# MCU_PWR.net
KiCad netlist of a schematic drawn in Altium Designer
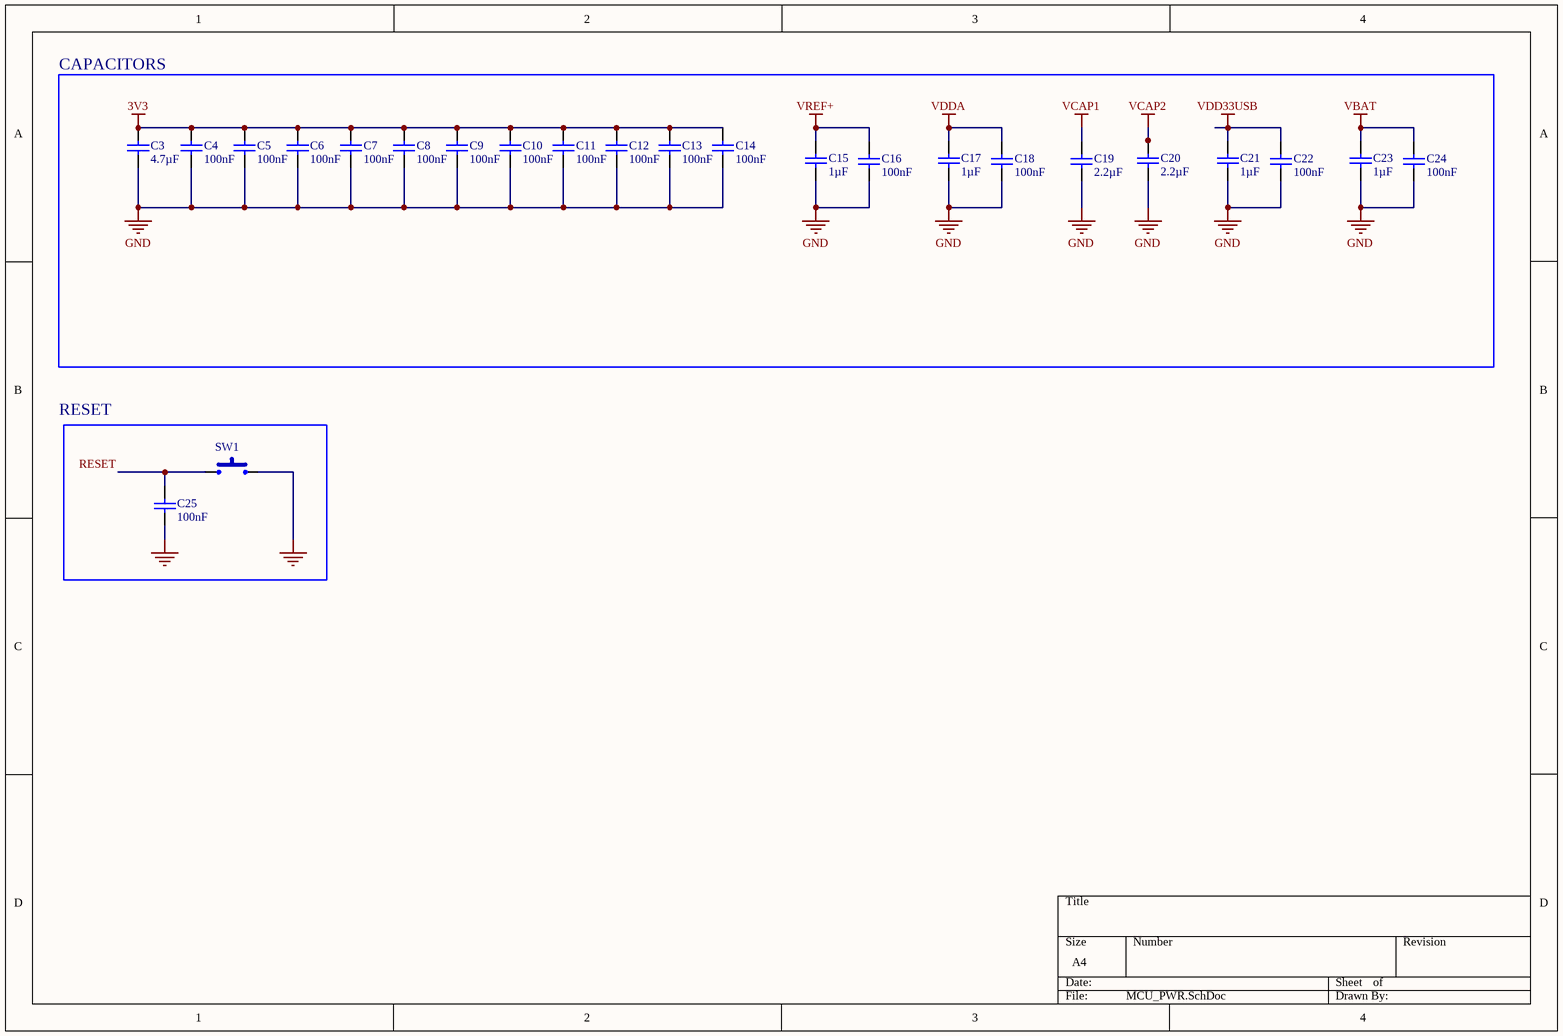
[diagram p0: MCU_PWR.SchDoc]

(export (version "E")
  (design (tool "Eeschema 10.0.6"))
  (components
    (comp (ref "C3")
      (value "4.7µF")
      (footprint "WCAP-CSGP_0603_L1.6W0.8H0.8_Reflow")
      (description "WCAP-CSGP Multilayer Ceramic Chip Capacitor, General Purpose, size 0603, X5R, 4.7uF, 10VDC")
      (fields
        (field (name "MANUFACTURER PART NUMBER") "885012106012")
        (field (name "MANUFACTURER") "Wurth Elektronik")
      )
      (libsource (lib "LEEM UPM") (part "885012209047R"))
    )
    (comp (ref "C4")
      (value "100nF")
      (footprint "WCAP-CSGP_0603_L1.6W0.8H0.8_Reflow")
      (description "WCAP-CSGP Multilayer Ceramic Chip Capacitor, General Purpose, size 0603, X7R, 100nF, 25VDC")
      (fields
        (field (name "MANUFACTURER") "Wurth Elektronik")
        (field (name "MANUFACTURER PART NUMBER") "885012206071")
      )
      (libsource (lib "LEEM UPM") (part "885012209047R"))
    )
    (comp (ref "C5")
      (value "100nF")
      (footprint "WCAP-CSGP_0603_L1.6W0.8H0.8_Reflow")
      (description "WCAP-CSGP Multilayer Ceramic Chip Capacitor, General Purpose, size 0603, X7R, 100nF, 25VDC")
      (fields
        (field (name "MANUFACTURER") "Wurth Elektronik")
        (field (name "MANUFACTURER PART NUMBER") "885012206071")
      )
      (libsource (lib "LEEM UPM") (part "885012209047R"))
    )
    (comp (ref "C6")
      (value "100nF")
      (footprint "WCAP-CSGP_0603_L1.6W0.8H0.8_Reflow")
      (description "WCAP-CSGP Multilayer Ceramic Chip Capacitor, General Purpose, size 0603, X7R, 100nF, 25VDC")
      (fields
        (field (name "MANUFACTURER") "Wurth Elektronik")
        (field (name "MANUFACTURER PART NUMBER") "885012206071")
      )
      (libsource (lib "LEEM UPM") (part "885012209047R"))
    )
    (comp (ref "C7")
      (value "100nF")
      (footprint "WCAP-CSGP_0603_L1.6W0.8H0.8_Reflow")
      (description "WCAP-CSGP Multilayer Ceramic Chip Capacitor, General Purpose, size 0603, X7R, 100nF, 25VDC")
      (fields
        (field (name "MANUFACTURER") "Wurth Elektronik")
        (field (name "MANUFACTURER PART NUMBER") "885012206071")
      )
      (libsource (lib "LEEM UPM") (part "885012209047R"))
    )
    (comp (ref "C8")
      (value "100nF")
      (footprint "WCAP-CSGP_0603_L1.6W0.8H0.8_Reflow")
      (description "WCAP-CSGP Multilayer Ceramic Chip Capacitor, General Purpose, size 0603, X7R, 100nF, 25VDC")
      (fields
        (field (name "MANUFACTURER") "Wurth Elektronik")
        (field (name "MANUFACTURER PART NUMBER") "885012206071")
      )
      (libsource (lib "LEEM UPM") (part "885012209047R"))
    )
    (comp (ref "C9")
      (value "100nF")
      (footprint "WCAP-CSGP_0603_L1.6W0.8H0.8_Reflow")
      (description "WCAP-CSGP Multilayer Ceramic Chip Capacitor, General Purpose, size 0603, X7R, 100nF, 25VDC")
      (fields
        (field (name "MANUFACTURER") "Wurth Elektronik")
        (field (name "MANUFACTURER PART NUMBER") "885012206071")
      )
      (libsource (lib "LEEM UPM") (part "885012209047R"))
    )
    (comp (ref "C10")
      (value "100nF")
      (footprint "WCAP-CSGP_0603_L1.6W0.8H0.8_Reflow")
      (description "WCAP-CSGP Multilayer Ceramic Chip Capacitor, General Purpose, size 0603, X7R, 100nF, 25VDC")
      (fields
        (field (name "MANUFACTURER") "Wurth Elektronik")
        (field (name "MANUFACTURER PART NUMBER") "885012206071")
      )
      (libsource (lib "LEEM UPM") (part "885012209047R"))
    )
    (comp (ref "C11")
      (value "100nF")
      (footprint "WCAP-CSGP_0603_L1.6W0.8H0.8_Reflow")
      (description "WCAP-CSGP Multilayer Ceramic Chip Capacitor, General Purpose, size 0603, X7R, 100nF, 25VDC")
      (fields
        (field (name "MANUFACTURER") "Wurth Elektronik")
        (field (name "MANUFACTURER PART NUMBER") "885012206071")
      )
      (libsource (lib "LEEM UPM") (part "885012209047R"))
    )
    (comp (ref "C12")
      (value "100nF")
      (footprint "WCAP-CSGP_0603_L1.6W0.8H0.8_Reflow")
      (description "WCAP-CSGP Multilayer Ceramic Chip Capacitor, General Purpose, size 0603, X7R, 100nF, 25VDC")
      (fields
        (field (name "MANUFACTURER") "Wurth Elektronik")
        (field (name "MANUFACTURER PART NUMBER") "885012206071")
      )
      (libsource (lib "LEEM UPM") (part "885012209047R"))
    )
    (comp (ref "C13")
      (value "100nF")
      (footprint "WCAP-CSGP_0603_L1.6W0.8H0.8_Reflow")
      (description "WCAP-CSGP Multilayer Ceramic Chip Capacitor, General Purpose, size 0603, X7R, 100nF, 25VDC")
      (fields
        (field (name "MANUFACTURER") "Wurth Elektronik")
        (field (name "MANUFACTURER PART NUMBER") "885012206071")
      )
      (libsource (lib "LEEM UPM") (part "885012209047R"))
    )
    (comp (ref "C14")
      (value "100nF")
      (footprint "WCAP-CSGP_0603_L1.6W0.8H0.8_Reflow")
      (description "WCAP-CSGP Multilayer Ceramic Chip Capacitor, General Purpose, size 0603, X7R, 100nF, 25VDC")
      (fields
        (field (name "MANUFACTURER") "Wurth Elektronik")
        (field (name "MANUFACTURER PART NUMBER") "885012206071")
      )
      (libsource (lib "LEEM UPM") (part "885012209047R"))
    )
    (comp (ref "C15")
      (value "1µF")
      (footprint "WCAP-CSGP_0603_L1.6W0.8H0.8_Reflow")
      (description "WCAP-CSGP Multilayer Ceramic Chip Capacitor, General Purpose, size 0603, X7R, 1uF, 16VDC")
      (fields
        (field (name "MANUFACTURER") "Wurth Elektronik")
        (field (name "MANUFACTURER PART NUMBER") "885012206052")
      )
      (libsource (lib "LEEM UPM") (part "885012209047R"))
    )
    (comp (ref "C16")
      (value "100nF")
      (footprint "WCAP-CSGP_0603_L1.6W0.8H0.8_Reflow")
      (description "WCAP-CSGP Multilayer Ceramic Chip Capacitor, General Purpose, size 0603, X7R, 100nF, 25VDC")
      (fields
        (field (name "MANUFACTURER") "Wurth Elektronik")
        (field (name "MANUFACTURER PART NUMBER") "885012206071")
      )
      (libsource (lib "LEEM UPM") (part "885012209047R"))
    )
    (comp (ref "C17")
      (value "1µF")
      (footprint "WCAP-CSGP_0603_L1.6W0.8H0.8_Reflow")
      (description "WCAP-CSGP Multilayer Ceramic Chip Capacitor, General Purpose, size 0603, X7R, 1uF, 16VDC")
      (fields
        (field (name "MANUFACTURER") "Wurth Elektronik")
        (field (name "MANUFACTURER PART NUMBER") "885012206052")
      )
      (libsource (lib "LEEM UPM") (part "885012209047R"))
    )
    (comp (ref "C18")
      (value "100nF")
      (footprint "WCAP-CSGP_0603_L1.6W0.8H0.8_Reflow")
      (description "WCAP-CSGP Multilayer Ceramic Chip Capacitor, General Purpose, size 0603, X7R, 100nF, 25VDC")
      (fields
        (field (name "MANUFACTURER") "Wurth Elektronik")
        (field (name "MANUFACTURER PART NUMBER") "885012206071")
      )
      (libsource (lib "LEEM UPM") (part "885012209047R"))
    )
    (comp (ref "C19")
      (value "2.2µF")
      (footprint "WCAP-CSGP_0603_L1.6W0.8H0.8_Reflow")
      (description "WCAP-CSGP Multilayer Ceramic Chip Capacitor, General Purpose, size 0603, X5R, 2.2uF, 16VDC")
      (fields
        (field (name "MANUFACTURER PART NUMBER") "885012106018")
        (field (name "MANUFACTURER") "Wurth Elektronik")
      )
      (libsource (lib "LEEM UPM") (part "885012209047R"))
    )
    (comp (ref "C20")
      (value "2.2µF")
      (footprint "WCAP-CSGP_0603_L1.6W0.8H0.8_Reflow")
      (description "WCAP-CSGP Multilayer Ceramic Chip Capacitor, General Purpose, size 0603, X5R, 2.2uF, 16VDC")
      (fields
        (field (name "MANUFACTURER PART NUMBER") "885012106018")
        (field (name "MANUFACTURER") "Wurth Elektronik")
      )
      (libsource (lib "LEEM UPM") (part "885012209047R"))
    )
    (comp (ref "C21")
      (value "1µF")
      (footprint "WCAP-CSGP_0603_L1.6W0.8H0.8_Reflow")
      (description "WCAP-CSGP Multilayer Ceramic Chip Capacitor, General Purpose, size 0603, X7R, 1uF, 16VDC")
      (fields
        (field (name "MANUFACTURER") "Wurth Elektronik")
        (field (name "MANUFACTURER PART NUMBER") "885012206052")
      )
      (libsource (lib "LEEM UPM") (part "885012209047R"))
    )
    (comp (ref "C22")
      (value "100nF")
      (footprint "WCAP-CSGP_0603_L1.6W0.8H0.8_Reflow")
      (description "WCAP-CSGP Multilayer Ceramic Chip Capacitor, General Purpose, size 0603, X7R, 100nF, 25VDC")
      (fields
        (field (name "MANUFACTURER") "Wurth Elektronik")
        (field (name "MANUFACTURER PART NUMBER") "885012206071")
      )
      (libsource (lib "LEEM UPM") (part "885012209047R"))
    )
    (comp (ref "C23")
      (value "1µF")
      (footprint "WCAP-CSGP_0603_L1.6W0.8H0.8_Reflow")
      (description "WCAP-CSGP Multilayer Ceramic Chip Capacitor, General Purpose, size 0603, X7R, 1uF, 16VDC")
      (fields
        (field (name "MANUFACTURER") "Wurth Elektronik")
        (field (name "MANUFACTURER PART NUMBER") "885012206052")
      )
      (libsource (lib "LEEM UPM") (part "885012209047R"))
    )
    (comp (ref "C24")
      (value "100nF")
      (footprint "WCAP-CSGP_0603_L1.6W0.8H0.8_Reflow")
      (description "WCAP-CSGP Multilayer Ceramic Chip Capacitor, General Purpose, size 0603, X7R, 100nF, 25VDC")
      (fields
        (field (name "MANUFACTURER") "Wurth Elektronik")
        (field (name "MANUFACTURER PART NUMBER") "885012206071")
      )
      (libsource (lib "LEEM UPM") (part "885012209047R"))
    )
    (comp (ref "C25")
      (value "100nF")
      (footprint "WCAP-CSGP_0603_L1.6W0.8H0.8_Reflow")
      (description "WCAP-CSGP Multilayer Ceramic Chip Capacitor, General Purpose, size 0603, X7R, 100nF, 25VDC")
      (fields
        (field (name "MANUFACTURER") "Wurth Elektronik")
        (field (name "MANUFACTURER PART NUMBER") "885012206071")
      )
      (libsource (lib "LEEM UPM") (part "885012209047R"))
    )
    (comp (ref "SW1")
      (value "PTS815SJM250SMTRLFS")
      (footprint "PTS815SJM250SMTRLFS-Footprint-1")
      (libsource (lib "LEEM UPM") (part "PTS815S"))
    )
  )
  (nets
    (net (code "1") (name "/RESET") (class "Default")
      (node (ref "C25") (pin "2") (pinfunction "2_2") (pintype "passive"))
      (node (ref "SW1") (pin "1") (pinfunction "1_1") (pintype "passive"))
    )
    (net (code "2") (name "3V3") (class "Default")
      (node (ref "C10") (pin "1") (pinfunction "1_1") (pintype "passive"))
      (node (ref "C11") (pin "1") (pinfunction "1_1") (pintype "passive"))
      (node (ref "C12") (pin "1") (pinfunction "1_1") (pintype "passive"))
      (node (ref "C13") (pin "1") (pinfunction "1_1") (pintype "passive"))
      (node (ref "C14") (pin "1") (pinfunction "1_1") (pintype "passive"))
      (node (ref "C3") (pin "1") (pinfunction "1_1") (pintype "passive"))
      (node (ref "C4") (pin "1") (pinfunction "1_1") (pintype "passive"))
      (node (ref "C5") (pin "1") (pinfunction "1_1") (pintype "passive"))
      (node (ref "C6") (pin "1") (pinfunction "1_1") (pintype "passive"))
      (node (ref "C7") (pin "1") (pinfunction "1_1") (pintype "passive"))
      (node (ref "C8") (pin "1") (pinfunction "1_1") (pintype "passive"))
      (node (ref "C9") (pin "1") (pinfunction "1_1") (pintype "passive"))
    )
    (net (code "3") (name "GND") (class "Default")
      (node (ref "C10") (pin "2") (pinfunction "2_2") (pintype "passive"))
      (node (ref "C11") (pin "2") (pinfunction "2_2") (pintype "passive"))
      (node (ref "C12") (pin "2") (pinfunction "2_2") (pintype "passive"))
      (node (ref "C13") (pin "2") (pinfunction "2_2") (pintype "passive"))
      (node (ref "C14") (pin "2") (pinfunction "2_2") (pintype "passive"))
      (node (ref "C15") (pin "2") (pinfunction "2_2") (pintype "passive"))
      (node (ref "C16") (pin "2") (pinfunction "2_2") (pintype "passive"))
      (node (ref "C17") (pin "2") (pinfunction "2_2") (pintype "passive"))
      (node (ref "C18") (pin "2") (pinfunction "2_2") (pintype "passive"))
      (node (ref "C19") (pin "1") (pinfunction "1_1") (pintype "passive"))
      (node (ref "C20") (pin "1") (pinfunction "1_1") (pintype "passive"))
      (node (ref "C21") (pin "2") (pinfunction "2_2") (pintype "passive"))
      (node (ref "C22") (pin "2") (pinfunction "2_2") (pintype "passive"))
      (node (ref "C23") (pin "2") (pinfunction "2_2") (pintype "passive"))
      (node (ref "C24") (pin "2") (pinfunction "2_2") (pintype "passive"))
      (node (ref "C25") (pin "1") (pinfunction "1_1") (pintype "passive"))
      (node (ref "C3") (pin "2") (pinfunction "2_2") (pintype "passive"))
      (node (ref "C4") (pin "2") (pinfunction "2_2") (pintype "passive"))
      (node (ref "C5") (pin "2") (pinfunction "2_2") (pintype "passive"))
      (node (ref "C6") (pin "2") (pinfunction "2_2") (pintype "passive"))
      (node (ref "C7") (pin "2") (pinfunction "2_2") (pintype "passive"))
      (node (ref "C8") (pin "2") (pinfunction "2_2") (pintype "passive"))
      (node (ref "C9") (pin "2") (pinfunction "2_2") (pintype "passive"))
      (node (ref "SW1") (pin "2") (pinfunction "2_2") (pintype "passive"))
    )
    (net (code "4") (name "VBAT") (class "Default")
      (node (ref "C23") (pin "1") (pinfunction "1_1") (pintype "passive"))
      (node (ref "C24") (pin "1") (pinfunction "1_1") (pintype "passive"))
    )
    (net (code "5") (name "VCAP1") (class "Default")
      (node (ref "C19") (pin "2") (pinfunction "2_2") (pintype "passive"))
    )
    (net (code "6") (name "VCAP2") (class "Default")
      (node (ref "C20") (pin "2") (pinfunction "2_2") (pintype "passive"))
    )
    (net (code "7") (name "VDD33USB") (class "Default")
      (node (ref "C21") (pin "1") (pinfunction "1_1") (pintype "passive"))
      (node (ref "C22") (pin "1") (pinfunction "1_1") (pintype "passive"))
    )
    (net (code "8") (name "VDDA") (class "Default")
      (node (ref "C17") (pin "1") (pinfunction "1_1") (pintype "passive"))
      (node (ref "C18") (pin "1") (pinfunction "1_1") (pintype "passive"))
    )
    (net (code "9") (name "VREF+") (class "Default")
      (node (ref "C15") (pin "1") (pinfunction "1_1") (pintype "passive"))
      (node (ref "C16") (pin "1") (pinfunction "1_1") (pintype "passive"))
    )
  )
)
